# PowerManager.net
KiCad netlist of a schematic drawn in Altium Designer
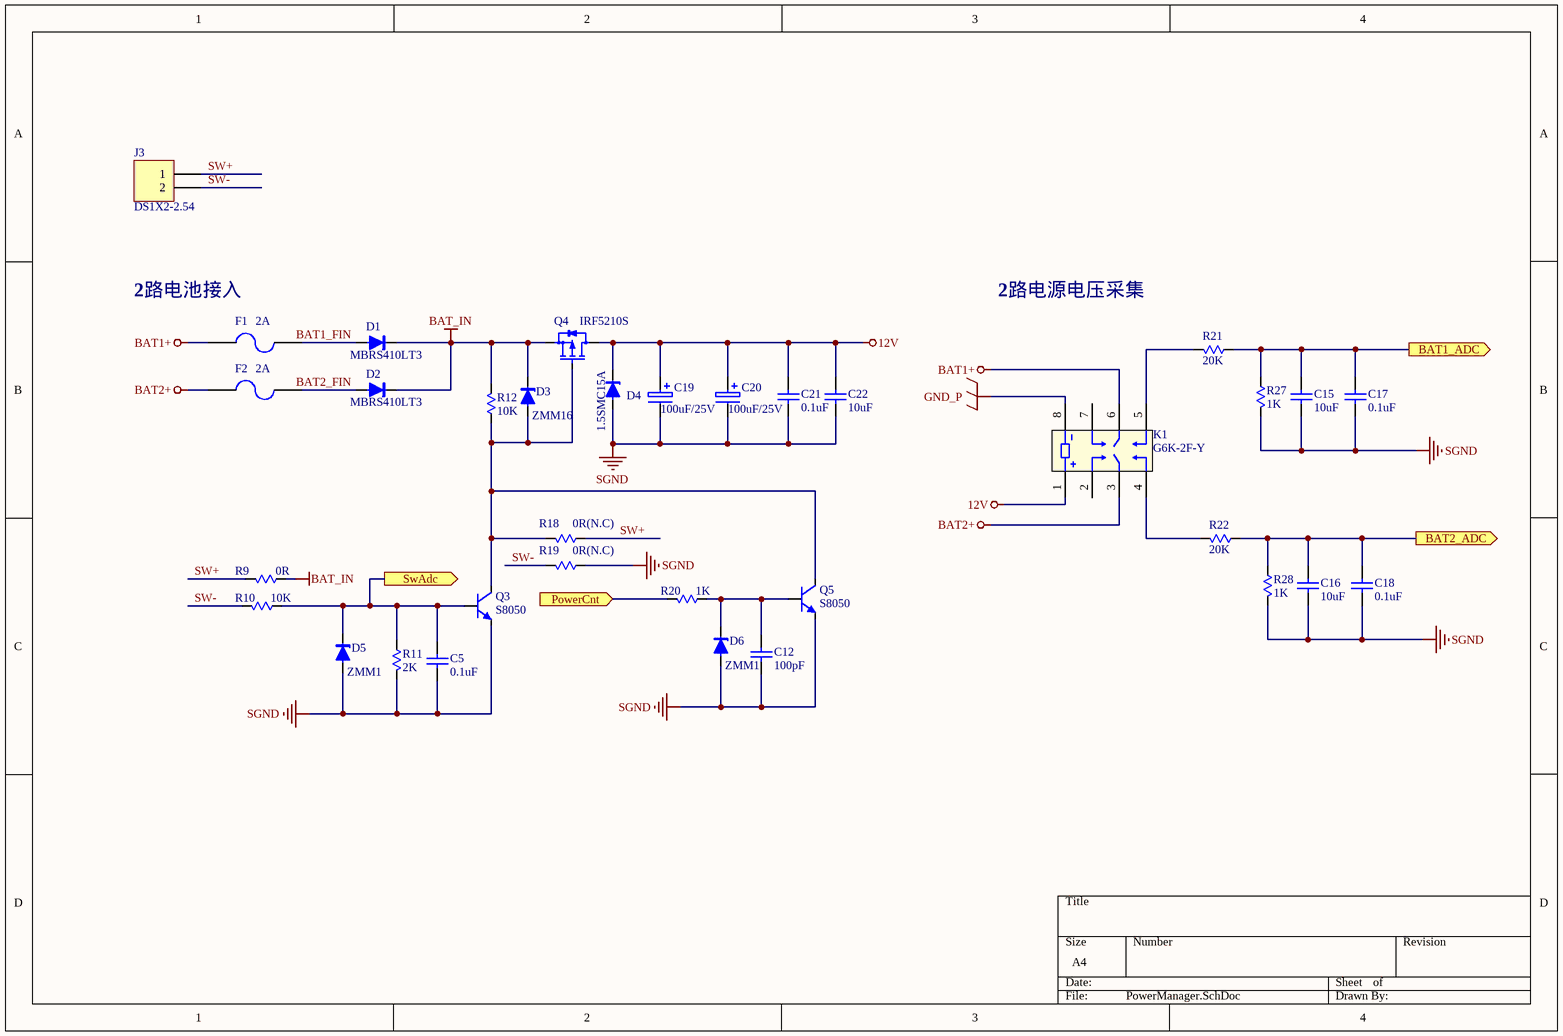
[diagram p0: PowerManager.SchDoc]

(export (version "E")
  (design (tool "Eeschema 10.0.6"))
  (components
    (comp (ref "C5")
      (value "0.1uF")
      (footprint "C0805")
      (description "Capacitor")
      (fields (field (name "PUBLISHER") "Altium Limited"))
      (libsource (lib "Miscellaneous Devices") (part "Cap"))
    )
    (comp (ref "C12")
      (value "100pF")
      (footprint "C0805")
      (description "Capacitor")
      (fields (field (name "PUBLISHER") "Altium Limited"))
      (libsource (lib "Miscellaneous Devices") (part "Cap"))
    )
    (comp (ref "C15")
      (value "10uF")
      (footprint "C0805")
      (description "CAP")
      (fields (field (name "PUBLISHER") "Altium Limited"))
      (libsource (lib "Passive Components Class") (part "CAP"))
    )
    (comp (ref "C16")
      (value "10uF")
      (footprint "C0805")
      (description "CAP")
      (fields (field (name "PUBLISHER") "Altium Limited"))
      (libsource (lib "Passive Components Class") (part "CAP"))
    )
    (comp (ref "C17")
      (value "0.1uF")
      (footprint "C0805")
      (description "CAP")
      (fields (field (name "PUBLISHER") "Altium Limited"))
      (libsource (lib "Passive Components Class") (part "CAP"))
    )
    (comp (ref "C18")
      (value "0.1uF")
      (footprint "C0805")
      (description "CAP")
      (fields (field (name "PUBLISHER") "Altium Limited"))
      (libsource (lib "Passive Components Class") (part "CAP"))
    )
    (comp (ref "C19")
      (value "100uF/25V")
      (footprint "CT7343-E-S")
      (description "Electrolytic Capacitor")
      (libsource (lib "*") (part "ELECTRO"))
    )
    (comp (ref "C20")
      (value "100uF/25V")
      (footprint "CT7343-E-S")
      (description "Electrolytic Capacitor")
      (libsource (lib "*") (part "ELECTRO"))
    )
    (comp (ref "C21")
      (value "0.1uF")
      (footprint "C0805")
      (description "Capacitor")
      (fields (field (name "PUBLISHER") "Altium Limited"))
      (libsource (lib "Miscellaneous Devices") (part "Cap"))
    )
    (comp (ref "C22")
      (value "10uF")
      (footprint "C0805")
      (description "Capacitor")
      (fields (field (name "PUBLISHER") "Altium Limited"))
      (libsource (lib "Miscellaneous Devices") (part "Cap"))
    )
    (comp (ref "D1")
      (value "MBRS410LT3")
      (footprint "SMC")
      (description "Small Signal Zener Diodes")
      (libsource (lib "Passive Components Class") (part "DIODE-ZENER"))
    )
    (comp (ref "D2")
      (value "MBRS410LT3")
      (footprint "SMC")
      (description "Small Signal Zener Diodes")
      (libsource (lib "Passive Components Class") (part "DIODE-ZENER"))
    )
    (comp (ref "D3")
      (value "ZMM16")
      (footprint "SOD-80")
      (description "Small Signal Zener Diodes")
      (libsource (lib "Passive Components Class") (part "DIODE-ZENER"))
    )
    (comp (ref "D4")
      (value "1.5SMC15A")
      (footprint "SMC")
      (description "Small Signal Zener Diodes")
      (libsource (lib "Passive Components Class") (part "DIODE-ZENER"))
    )
    (comp (ref "D5")
      (value "ZMM1")
      (footprint "SOD-80")
      (description "Small Signal Zener Diodes")
      (libsource (lib "Passive Components Class") (part "DIODE-ZENER"))
    )
    (comp (ref "D6")
      (value "ZMM1")
      (footprint "SOD-80")
      (description "Small Signal Zener Diodes")
      (libsource (lib "Passive Components Class") (part "DIODE-ZENER"))
    )
    (comp (ref "F1")
      (value "2A")
      (footprint "F1812")
      (description "Fuse")
      (libsource (lib "*") (part "FUSE2"))
    )
    (comp (ref "F2")
      (value "2A")
      (footprint "F1812")
      (description "Fuse")
      (libsource (lib "*") (part "FUSE2"))
    )
    (comp (ref "J3")
      (value "DS1X2-2.54")
      (footprint "ZH1X2WT-1.5")
      (description "Header, 2-Pin")
      (fields (field (name "PUBLISHER") "Altium Limited"))
      (libsource (lib "Miscellaneous Connectors") (part "Header 2"))
    )
    (comp (ref "K1")
      (value "G6K-2F-Y")
      (footprint "G6K-2F-Y")
      (libsource (lib "Productor Class") (part "G6K-2F-Y"))
    )
    (comp (ref "Q3")
      (value "S8050")
      (footprint "SOT-23")
      (description "NPN General Purpose Amplifier")
      (fields (field (name "PUBLISHER") "Altium Limited"))
      (libsource (lib "Bdmc4810") (part "NPN"))
    )
    (comp (ref "Q4")
      (value "IRF5210S")
      (footprint "TO-262")
      (description "P-Channel 30-V (D-S), 150 C MOSFET")
      (libsource (lib "Passive Components Class") (part "PMOS"))
    )
    (comp (ref "Q5")
      (value "S8050")
      (footprint "SOT-23")
      (description "NPN General Purpose Amplifier")
      (fields (field (name "PUBLISHER") "Altium Limited"))
      (libsource (lib "Bdmc4810") (part "NPN"))
    )
    (comp (ref "R9")
      (value "0R")
      (footprint "R0805")
      (description "Resistor")
      (fields (field (name "PUBLISHER") "Altium Limited"))
      (libsource (lib "Temp") (part "Res"))
    )
    (comp (ref "R10")
      (value "10K")
      (footprint "R0805")
      (description "Resistor")
      (fields (field (name "PUBLISHER") "Altium Limited"))
      (libsource (lib "Temp") (part "Res"))
    )
    (comp (ref "R11")
      (value "2K")
      (footprint "R0805")
      (description "Resistor")
      (fields (field (name "PUBLISHER") "Altium Limited"))
      (libsource (lib "Temp") (part "Res"))
    )
    (comp (ref "R12")
      (value "10K")
      (footprint "R0805")
      (description "Resistor")
      (fields (field (name "PUBLISHER") "Altium Limited"))
      (libsource (lib "Temp") (part "Res"))
    )
    (comp (ref "R18")
      (value "0R(N.C)")
      (footprint "R0805")
      (description "Resistor")
      (fields (field (name "PUBLISHER") "Altium Limited"))
      (libsource (lib "Passive Components Class") (part "RES"))
    )
    (comp (ref "R19")
      (value "0R(N.C)")
      (footprint "R0805")
      (description "Resistor")
      (fields (field (name "PUBLISHER") "Altium Limited"))
      (libsource (lib "Passive Components Class") (part "RES"))
    )
    (comp (ref "R20")
      (value "1K")
      (footprint "R0805")
      (description "Resistor")
      (fields (field (name "PUBLISHER") "Altium Limited"))
      (libsource (lib "Temp") (part "Res"))
    )
    (comp (ref "R21")
      (value "20K")
      (footprint "R0805")
      (description "Resistor")
      (fields (field (name "PUBLISHER") "Altium Limited"))
      (libsource (lib "") (part "RES_1"))
    )
    (comp (ref "R22")
      (value "20K")
      (footprint "R0805")
      (description "Resistor")
      (fields (field (name "PUBLISHER") "Altium Limited"))
      (libsource (lib "") (part "RES_1"))
    )
    (comp (ref "R27")
      (value "1K")
      (footprint "R0805")
      (description "Resistor")
      (fields (field (name "PUBLISHER") "Altium Limited"))
      (libsource (lib "") (part "RES_1"))
    )
    (comp (ref "R28")
      (value "1K")
      (footprint "R0805")
      (description "Resistor")
      (fields (field (name "PUBLISHER") "Altium Limited"))
      (libsource (lib "") (part "RES_1"))
    )
  )
  (nets
    (net (code "1") (name "/BAT1_ADC") (class "Default")
      (node (ref "C15") (pin "1") (pinfunction "1_1") (pintype "passive"))
      (node (ref "C17") (pin "1") (pinfunction "1_1") (pintype "passive"))
      (node (ref "R21") (pin "2") (pinfunction "2_2") (pintype "passive"))
      (node (ref "R27") (pin "2") (pinfunction "2_2") (pintype "passive"))
    )
    (net (code "3") (name "/BAT2_ADC") (class "Default")
      (node (ref "C16") (pin "1") (pinfunction "1_1") (pintype "passive"))
      (node (ref "C18") (pin "1") (pinfunction "1_1") (pintype "passive"))
      (node (ref "R22") (pin "2") (pinfunction "2_2") (pintype "passive"))
      (node (ref "R28") (pin "2") (pinfunction "2_2") (pintype "passive"))
    )
    (net (code "5") (name "/PowerCnt") (class "Default")
      (node (ref "R20") (pin "1") (pinfunction "1_1") (pintype "passive"))
    )
    (net (code "6") (name "/SW+") (class "Default")
      (node (ref "J3") (pin "1") (pinfunction "1_1") (pintype "passive"))
      (node (ref "R18") (pin "1") (pinfunction "1_1") (pintype "passive"))
      (node (ref "R9") (pin "1") (pinfunction "1_1") (pintype "passive"))
    )
    (net (code "7") (name "/SW-") (class "Default")
      (node (ref "J3") (pin "2") (pinfunction "2_2") (pintype "passive"))
      (node (ref "R10") (pin "1") (pinfunction "1_1") (pintype "passive"))
      (node (ref "R19") (pin "2") (pinfunction "2_2") (pintype "passive"))
    )
    (net (code "8") (name "/SwAdc") (class "Default")
      (node (ref "C5") (pin "2") (pinfunction "2_2") (pintype "passive"))
      (node (ref "D5") (pin "2") (pinfunction "K_2") (pintype "passive"))
      (node (ref "Q3") (pin "1") (pinfunction "B_1") (pintype "passive"))
      (node (ref "R10") (pin "2") (pinfunction "2_2") (pintype "passive"))
      (node (ref "R11") (pin "2") (pinfunction "2_2") (pintype "passive"))
    )
    (net (code "9") (name "12V") (class "Default")
      (node (ref "C19") (pin "1") (pinfunction "1_1") (pintype "passive"))
      (node (ref "C20") (pin "1") (pinfunction "1_1") (pintype "passive"))
      (node (ref "C21") (pin "2") (pinfunction "2_2") (pintype "passive"))
      (node (ref "C22") (pin "2") (pinfunction "2_2") (pintype "passive"))
      (node (ref "D4") (pin "2") (pinfunction "K_2") (pintype "passive"))
      (node (ref "K1") (pin "1") (pinfunction "1_1") (pintype "passive"))
      (node (ref "Q4") (pin "2") (pinfunction "D_2") (pintype "passive"))
    )
    (net (code "10") (name "BAT1+") (class "Default")
      (node (ref "F1") (pin "1") (pinfunction "1_1") (pintype "passive"))
      (node (ref "K1") (pin "6") (pinfunction "6_6") (pintype "passive"))
    )
    (net (code "11") (name "BAT2+") (class "Default")
      (node (ref "F2") (pin "1") (pinfunction "1_1") (pintype "passive"))
      (node (ref "K1") (pin "3") (pinfunction "3_3") (pintype "passive"))
    )
    (net (code "12") (name "BAT_IN") (class "Default")
      (node (ref "D1") (pin "2") (pinfunction "K_2") (pintype "passive"))
      (node (ref "D2") (pin "2") (pinfunction "K_2") (pintype "passive"))
      (node (ref "D3") (pin "2") (pinfunction "K_2") (pintype "passive"))
      (node (ref "Q4") (pin "3") (pinfunction "S_3") (pintype "passive"))
      (node (ref "R12") (pin "1") (pinfunction "1_1") (pintype "passive"))
      (node (ref "R9") (pin "2") (pinfunction "2_2") (pintype "passive"))
    )
    (net (code "13") (name "GND_P") (class "Default")
      (node (ref "K1") (pin "8") (pinfunction "8_8") (pintype "passive"))
    )
    (net (code "14") (name "Net-(D1-A)") (class "Default")
      (node (ref "D1") (pin "1") (pinfunction "A_1") (pintype "passive"))
      (node (ref "F1") (pin "2") (pinfunction "2_2") (pintype "passive"))
    )
    (net (code "15") (name "Net-(D2-A)") (class "Default")
      (node (ref "D2") (pin "1") (pinfunction "A_1") (pintype "passive"))
      (node (ref "F2") (pin "2") (pinfunction "2_2") (pintype "passive"))
    )
    (net (code "16") (name "Net-(D3-A)") (class "Default")
      (node (ref "D3") (pin "1") (pinfunction "A_1") (pintype "passive"))
      (node (ref "Q3") (pin "3") (pinfunction "C_3") (pintype "passive"))
      (node (ref "Q4") (pin "1") (pinfunction "G_1") (pintype "passive"))
      (node (ref "Q5") (pin "3") (pinfunction "C_3") (pintype "passive"))
      (node (ref "R12") (pin "2") (pinfunction "2_2") (pintype "passive"))
      (node (ref "R18") (pin "2") (pinfunction "2_2") (pintype "passive"))
    )
    (net (code "17") (name "Net-(D6-K)") (class "Default")
      (node (ref "C12") (pin "2") (pinfunction "2_2") (pintype "passive"))
      (node (ref "D6") (pin "2") (pinfunction "K_2") (pintype "passive"))
      (node (ref "Q5") (pin "1") (pinfunction "B_1") (pintype "passive"))
      (node (ref "R20") (pin "2") (pinfunction "2_2") (pintype "passive"))
    )
    (net (code "18") (name "Net-(K1-Pad4)") (class "Default")
      (node (ref "K1") (pin "4") (pinfunction "4_4") (pintype "passive"))
      (node (ref "R22") (pin "1") (pinfunction "1_1") (pintype "passive"))
    )
    (net (code "19") (name "Net-(K1-Pad5)") (class "Default")
      (node (ref "K1") (pin "5") (pinfunction "5_5") (pintype "passive"))
      (node (ref "R21") (pin "1") (pinfunction "1_1") (pintype "passive"))
    )
    (net (code "20") (name "SGND") (class "Default")
      (node (ref "C12") (pin "1") (pinfunction "1_1") (pintype "passive"))
      (node (ref "C15") (pin "2") (pinfunction "2_2") (pintype "passive"))
      (node (ref "C16") (pin "2") (pinfunction "2_2") (pintype "passive"))
      (node (ref "C17") (pin "2") (pinfunction "2_2") (pintype "passive"))
      (node (ref "C18") (pin "2") (pinfunction "2_2") (pintype "passive"))
      (node (ref "C19") (pin "2") (pinfunction "2_2") (pintype "passive"))
      (node (ref "C20") (pin "2") (pinfunction "2_2") (pintype "passive"))
      (node (ref "C21") (pin "1") (pinfunction "1_1") (pintype "passive"))
      (node (ref "C22") (pin "1") (pinfunction "1_1") (pintype "passive"))
      (node (ref "C5") (pin "1") (pinfunction "1_1") (pintype "passive"))
      (node (ref "D4") (pin "1") (pinfunction "A_1") (pintype "passive"))
      (node (ref "D5") (pin "1") (pinfunction "A_1") (pintype "passive"))
      (node (ref "D6") (pin "1") (pinfunction "A_1") (pintype "passive"))
      (node (ref "Q3") (pin "2") (pinfunction "E_2") (pintype "passive"))
      (node (ref "Q5") (pin "2") (pinfunction "E_2") (pintype "passive"))
      (node (ref "R11") (pin "1") (pinfunction "1_1") (pintype "passive"))
      (node (ref "R19") (pin "1") (pinfunction "1_1") (pintype "passive"))
      (node (ref "R27") (pin "1") (pinfunction "1_1") (pintype "passive"))
      (node (ref "R28") (pin "1") (pinfunction "1_1") (pintype "passive"))
    )
    (net (code "21") (name "unconnected-(K1-Pad2)") (class "Default")
      (node (ref "K1") (pin "2") (pinfunction "2_2") (pintype "passive"))
    )
    (net (code "22") (name "unconnected-(K1-Pad7)") (class "Default")
      (node (ref "K1") (pin "7") (pinfunction "7_7") (pintype "passive"))
    )
  )
)
